# User_Interface.net
KiCad netlist of a schematic drawn in Altium Designer
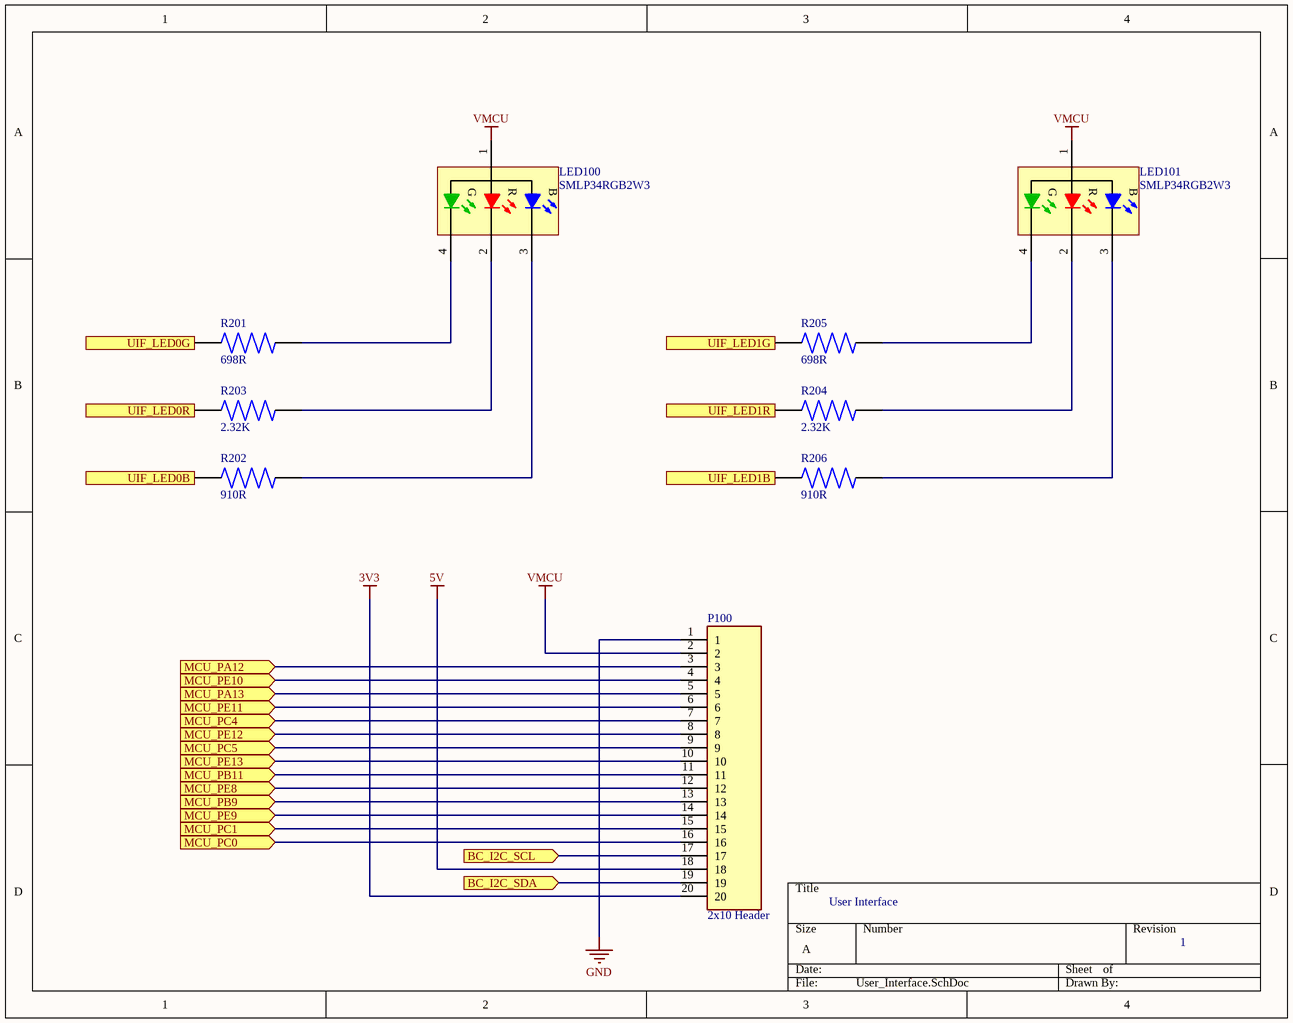
[diagram p0: User_Interface.SchDoc]

(export (version "E")
  (design (tool "Eeschema 10.0.6"))
  (components
    (comp (ref "LED100")
      (value "SMLP34RGB2W3")
      (footprint "ROHM-SMLP34-4_V")
      (description "PICOLED-RGB LED, 5 mA, -40 to 85 degC, 4-Pin 1 x 1 x 0.25 mm SMD, RoHS, Tape and Reel")
      (fields (field (name "MANUFACTURER") "ROHM Semiconductor"))
      (libsource (lib "nnts") (part "SMLP34RGB2W3"))
    )
    (comp (ref "LED101")
      (value "SMLP34RGB2W3")
      (footprint "ROHM-SMLP34-4_V")
      (description "PICOLED-RGB LED, 5 mA, -40 to 85 degC, 4-Pin 1 x 1 x 0.25 mm SMD, RoHS, Tape and Reel")
      (fields (field (name "MANUFACTURER") "ROHM Semiconductor"))
      (libsource (lib "nnts") (part "SMLP34RGB2W3"))
    )
    (comp (ref "P100")
      (value "2x10 Header")
      (footprint "2x10 Header")
      (description "HE2P-20G6C394-5R, 2.54 mm pegs.")
      (fields (field (name "MP") "1-826944-0") (field (name "MF") "TE Connectivity"))
      (libsource (lib "nnts") (part "2x10 Header"))
    )
    (comp (ref "R201")
      (value "698R")
      (footprint "R0603 Vishay")
      (description "RES SMD 698 OHM 1% 1/20W 0201")
      (fields
        (field (name "MANUFACTURER") "Vishay")
        (field (name "MANUFACTURER PART NUMBER") "CRCW0201698RFNED")
      )
      (libsource (lib "nnts") (part "CRCW0201698RFNED"))
    )
    (comp (ref "R202")
      (value "910R")
      (footprint "R0402 Vishay")
      (description "Res Thick Film 0402 910 Ohm 1% 0.063W(1/16W) ±100ppm/C Pad SMD Automotive T/R")
      (fields
        (field (name "MANUFACTURER") "Vishay")
        (field (name "MANUFACTURER PART NUMBER") "CRCW0402910RFKED")
      )
      (libsource (lib "nnts") (part "CRCW0402910RFKED"))
    )
    (comp (ref "R203")
      (value "2.32K")
      (footprint "R0805 Vishay")
      (description "VISHAY - CRCW08052K32FKEA - RES, THICK FILM, 2K32, 1%, 0.125W, 0805")
      (fields
        (field (name "MANUFACTURER") "Vishay")
        (field (name "MANUFACTURER PART NUMBER") "CRCW08052K32FKEA")
      )
      (libsource (lib "nnts") (part "CRCW08052K32FKEA"))
    )
    (comp (ref "R204")
      (value "2.32K")
      (footprint "R0805 Vishay")
      (description "VISHAY - CRCW08052K32FKEA - RES, THICK FILM, 2K32, 1%, 0.125W, 0805")
      (fields
        (field (name "MANUFACTURER") "Vishay")
        (field (name "MANUFACTURER PART NUMBER") "CRCW08052K32FKEA")
      )
      (libsource (lib "nnts") (part "CRCW08052K32FKEA"))
    )
    (comp (ref "R205")
      (value "698R")
      (footprint "R0603 Vishay")
      (description "RES SMD 698 OHM 1% 1/20W 0201")
      (fields
        (field (name "MANUFACTURER") "Vishay")
        (field (name "MANUFACTURER PART NUMBER") "CRCW0201698RFNED")
      )
      (libsource (lib "nnts") (part "CRCW0201698RFNED"))
    )
    (comp (ref "R206")
      (value "910R")
      (footprint "R0402 Vishay")
      (description "Res Thick Film 0402 910 Ohm 1% 0.063W(1/16W) ±100ppm/C Pad SMD Automotive T/R")
      (fields
        (field (name "MANUFACTURER") "Vishay")
        (field (name "MANUFACTURER PART NUMBER") "CRCW0402910RFKED")
      )
      (libsource (lib "nnts") (part "CRCW0402910RFKED"))
    )
  )
  (nets
    (net (code "1") (name "/BC_I2C_SCL") (class "Default")
      (node (ref "P100") (pin "17") (pinfunction "17_17") (pintype "passive"))
    )
    (net (code "2") (name "/BC_I2C_SDA") (class "Default")
      (node (ref "P100") (pin "19") (pinfunction "19_19") (pintype "passive"))
    )
    (net (code "3") (name "/MCU_PA12") (class "Default")
      (node (ref "P100") (pin "3") (pinfunction "3_3") (pintype "passive"))
    )
    (net (code "4") (name "/MCU_PA13") (class "Default")
      (node (ref "P100") (pin "5") (pinfunction "5_5") (pintype "passive"))
    )
    (net (code "5") (name "/MCU_PB9") (class "Default")
      (node (ref "P100") (pin "13") (pinfunction "13_13") (pintype "passive"))
    )
    (net (code "6") (name "/MCU_PB11") (class "Default")
      (node (ref "P100") (pin "11") (pinfunction "11_11") (pintype "passive"))
    )
    (net (code "7") (name "/MCU_PC0") (class "Default")
      (node (ref "P100") (pin "16") (pinfunction "16_16") (pintype "passive"))
    )
    (net (code "8") (name "/MCU_PC1") (class "Default")
      (node (ref "P100") (pin "15") (pinfunction "15_15") (pintype "passive"))
    )
    (net (code "9") (name "/MCU_PC4") (class "Default")
      (node (ref "P100") (pin "7") (pinfunction "7_7") (pintype "passive"))
    )
    (net (code "10") (name "/MCU_PC5") (class "Default")
      (node (ref "P100") (pin "9") (pinfunction "9_9") (pintype "passive"))
    )
    (net (code "11") (name "/MCU_PE8") (class "Default")
      (node (ref "P100") (pin "12") (pinfunction "12_12") (pintype "passive"))
    )
    (net (code "12") (name "/MCU_PE9") (class "Default")
      (node (ref "P100") (pin "14") (pinfunction "14_14") (pintype "passive"))
    )
    (net (code "13") (name "/MCU_PE10") (class "Default")
      (node (ref "P100") (pin "4") (pinfunction "4_4") (pintype "passive"))
    )
    (net (code "14") (name "/MCU_PE11") (class "Default")
      (node (ref "P100") (pin "6") (pinfunction "6_6") (pintype "passive"))
    )
    (net (code "15") (name "/MCU_PE12") (class "Default")
      (node (ref "P100") (pin "8") (pinfunction "8_8") (pintype "passive"))
    )
    (net (code "16") (name "/MCU_PE13") (class "Default")
      (node (ref "P100") (pin "10") (pinfunction "10_10") (pintype "passive"))
    )
    (net (code "17") (name "/UIF_LED0B") (class "Default")
      (node (ref "R202") (pin "1") (pinfunction "1_1") (pintype "passive"))
    )
    (net (code "18") (name "/UIF_LED0G") (class "Default")
      (node (ref "R201") (pin "1") (pinfunction "1_1") (pintype "passive"))
    )
    (net (code "19") (name "/UIF_LED0R") (class "Default")
      (node (ref "R203") (pin "1") (pinfunction "1_1") (pintype "passive"))
    )
    (net (code "20") (name "/UIF_LED1B") (class "Default")
      (node (ref "R206") (pin "1") (pinfunction "1_1") (pintype "passive"))
    )
    (net (code "21") (name "/UIF_LED1G") (class "Default")
      (node (ref "R205") (pin "1") (pinfunction "1_1") (pintype "passive"))
    )
    (net (code "22") (name "/UIF_LED1R") (class "Default")
      (node (ref "R204") (pin "1") (pinfunction "1_1") (pintype "passive"))
    )
    (net (code "23") (name "3V3") (class "Default")
      (node (ref "P100") (pin "20") (pinfunction "20_20") (pintype "passive"))
    )
    (net (code "24") (name "5V") (class "Default")
      (node (ref "P100") (pin "18") (pinfunction "18_18") (pintype "passive"))
    )
    (net (code "25") (name "GND") (class "Default")
      (node (ref "P100") (pin "1") (pinfunction "1_1") (pintype "passive"))
    )
    (net (code "26") (name "Net-(LED100-B)") (class "Default")
      (node (ref "LED100") (pin "3") (pinfunction "B_3") (pintype "passive"))
      (node (ref "R202") (pin "2") (pinfunction "2_2") (pintype "passive"))
    )
    (net (code "27") (name "Net-(LED100-G)") (class "Default")
      (node (ref "LED100") (pin "4") (pinfunction "G_4") (pintype "passive"))
      (node (ref "R201") (pin "2") (pinfunction "2_2") (pintype "passive"))
    )
    (net (code "28") (name "Net-(LED100-R)") (class "Default")
      (node (ref "LED100") (pin "2") (pinfunction "R_2") (pintype "passive"))
      (node (ref "R203") (pin "2") (pinfunction "2_2") (pintype "passive"))
    )
    (net (code "29") (name "Net-(LED101-B)") (class "Default")
      (node (ref "LED101") (pin "3") (pinfunction "B_3") (pintype "passive"))
      (node (ref "R206") (pin "2") (pinfunction "2_2") (pintype "passive"))
    )
    (net (code "30") (name "Net-(LED101-G)") (class "Default")
      (node (ref "LED101") (pin "4") (pinfunction "G_4") (pintype "passive"))
      (node (ref "R205") (pin "2") (pinfunction "2_2") (pintype "passive"))
    )
    (net (code "31") (name "Net-(LED101-R)") (class "Default")
      (node (ref "LED101") (pin "2") (pinfunction "R_2") (pintype "passive"))
      (node (ref "R204") (pin "2") (pinfunction "2_2") (pintype "passive"))
    )
    (net (code "32") (name "VMCU") (class "Default")
      (node (ref "LED100") (pin "1") (pinfunction "A_1") (pintype "passive"))
      (node (ref "LED101") (pin "1") (pinfunction "A_1") (pintype "passive"))
      (node (ref "P100") (pin "2") (pinfunction "2_2") (pintype "passive"))
    )
  )
)
